# Sensors.net
KiCad netlist of a schematic drawn in Altium Designer
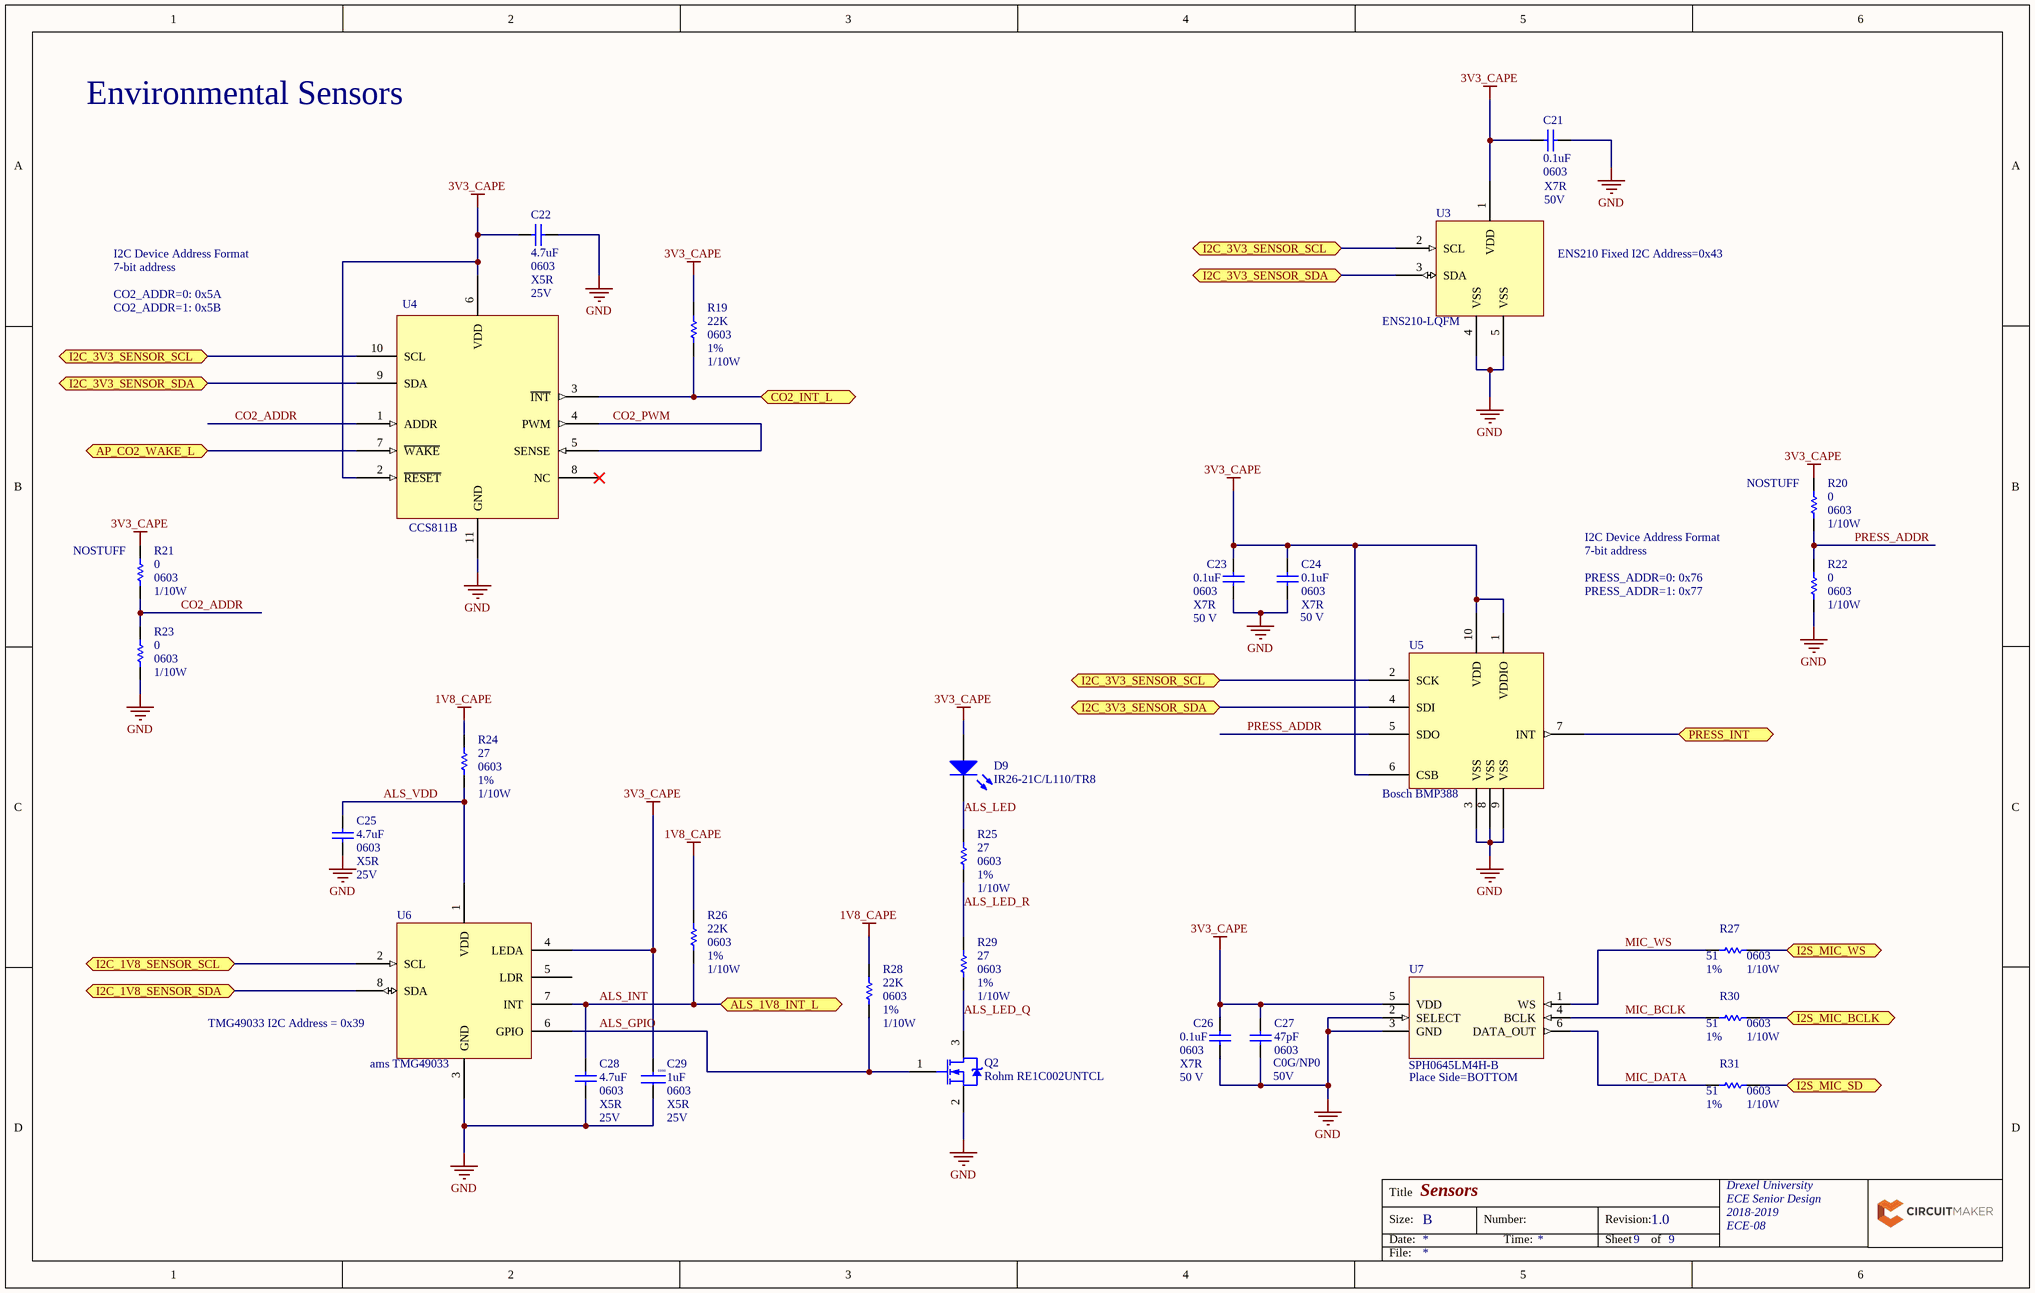
[diagram p0: Sensors.SchDoc]

(export (version "E")
  (design (tool "Eeschema 10.0.6"))
  (components
    (comp (ref "C21")
      (value "Yageo CC0603JRX7R9BB104")
      (footprint "PCB-8khfq59xjr5zuwyx680t-1")
      (description "0603 0.1 uF 50 V ±5 % Tolerance X7R SMT Multilayer Ceramic Capacitor")
      (fields
        (field (name "MANUFACTURER PART NUMBER") "CC0603JRX7R9BB104")
        (field (name "CAPACITANCE") "0.1uF")
        (field (name "CASE/PACKAGE") "0603")
        (field (name "VOLTAGE RATING (DC)") "50V")
        (field (name "DIELECTRIC CHARACTERISTIC") "X7R")
      )
      (libsource (lib "CommunityVault") (part "CMP-d32a1ae46a380ced-1"))
    )
    (comp (ref "C22")
      (value "Murata GRM188R61E475KE11D")
      (footprint "CAPC1608X90X35ML10T15")
      (description "CAP CER 4.7UF 25V 10% X5R 0603")
      (fields
        (field (name "CAPACITANCE") "4.7uF")
        (field (name "CASE/PACKAGE") "0603")
        (field (name "DIELECTRIC CHARACTERISTIC") "X5R")
        (field (name "VOLTAGE RATING (DC)") "25V")
        (field (name "MANUFACTURER PART NUMBER") "GRM188R61E475KE11D")
      )
      (libsource (lib "CommunityVault") (part "CMP-8856396-4"))
    )
    (comp (ref "C23")
      (value "Yageo CC0603JRX7R9BB104")
      (footprint "PCB-8khfq59xjr5zuwyx680t-1")
      (description "0603 0.1 uF 50 V ±5 % Tolerance X7R SMT Multilayer Ceramic Capacitor")
      (fields
        (field (name "MANUFACTURER PART NUMBER") "CC0603JRX7R9BB104")
        (field (name "CAPACITANCE") "0.1uF")
        (field (name "CASE/PACKAGE") "0603")
        (field (name "VOLTAGE RATING (DC)") "50 V")
        (field (name "DIELECTRIC CHARACTERISTIC") "X7R")
      )
      (libsource (lib "CommunityVault") (part "CMP-d32a1ae46a380ced-1"))
    )
    (comp (ref "C24")
      (value "Yageo CC0603JRX7R9BB104")
      (footprint "PCB-8khfq59xjr5zuwyx680t-1")
      (description "0603 0.1 uF 50 V ±5 % Tolerance X7R SMT Multilayer Ceramic Capacitor")
      (fields
        (field (name "MANUFACTURER PART NUMBER") "CC0603JRX7R9BB104")
        (field (name "CAPACITANCE") "0.1uF")
        (field (name "CASE/PACKAGE") "0603")
        (field (name "VOLTAGE RATING (DC)") "50 V")
        (field (name "DIELECTRIC CHARACTERISTIC") "X7R")
      )
      (libsource (lib "CommunityVault") (part "CMP-d32a1ae46a380ced-1"))
    )
    (comp (ref "C25")
      (value "Murata GRM188R61E475KE11D")
      (footprint "CAPC1608X90X35ML10T15")
      (description "CAP CER 4.7UF 25V 10% X5R 0603")
      (fields
        (field (name "CAPACITANCE") "4.7uF")
        (field (name "CASE/PACKAGE") "0603")
        (field (name "DIELECTRIC CHARACTERISTIC") "X5R")
        (field (name "VOLTAGE RATING (DC)") "25V")
        (field (name "MANUFACTURER PART NUMBER") "GRM188R61E475KE11D")
      )
      (libsource (lib "CommunityVault") (part "CMP-8856396-4"))
    )
    (comp (ref "C26")
      (value "Yageo CC0603JRX7R9BB104")
      (footprint "PCB-8khfq59xjr5zuwyx680t-1")
      (description "0603 0.1 uF 50 V ±5 % Tolerance X7R SMT Multilayer Ceramic Capacitor")
      (fields
        (field (name "MANUFACTURER PART NUMBER") "CC0603JRX7R9BB104")
        (field (name "CAPACITANCE") "0.1uF")
        (field (name "CASE/PACKAGE") "0603")
        (field (name "VOLTAGE RATING (DC)") "50 V")
        (field (name "DIELECTRIC CHARACTERISTIC") "X7R")
      )
      (libsource (lib "CommunityVault") (part "CMP-d32a1ae46a380ced-1"))
    )
    (comp (ref "C27")
      (value "Würth Elektronik 885012006055")
      (footprint "PCB-6hp2bdit6vqlyhs5eujf-1")
      (description "Cap, Mlcc, Np0, 47Pf, 50V, 0603")
      (fields
        (field (name "MANUFACTURER PART NUMBER") "885012006055")
        (field (name "CAPACITANCE") "47pF")
        (field (name "DIELECTRIC CHARACTERISTIC") "C0G/NP0")
        (field (name "VOLTAGE RATING (DC)") "50V")
        (field (name "PACKAGE") "0603")
      )
      (libsource (lib "CommunityVault") (part "CMP-bdcf7723a1936208-1"))
    )
    (comp (ref "C28")
      (value "Murata GRM188R61E475KE11D")
      (footprint "CAPC1608X90X35ML10T15")
      (description "CAP CER 4.7UF 25V 10% X5R 0603")
      (fields
        (field (name "CAPACITANCE") "4.7uF")
        (field (name "CASE/PACKAGE") "0603")
        (field (name "DIELECTRIC CHARACTERISTIC") "X5R")
        (field (name "VOLTAGE RATING (DC)") "25V")
        (field (name "MANUFACTURER PART NUMBER") "GRM188R61E475KE11D")
      )
      (libsource (lib "CommunityVault") (part "CMP-8856396-4"))
    )
    (comp (ref "C29")
      (value "Taiyo Yuden TMK107BJ105KA-T")
      (footprint "PCB-bncvufzharetcg4gy1u6-1")
      (description "Cap Ceramic 1uF 25V X5R 10% SMD 0603 85°C Paper T/R")
      (fields
        (field (name "CASE/PACKAGE") "0603")
        (field (name "DIELECTRIC CHARACTERISTIC") "X5R")
        (field (name "CAPACITANCE") "1uF")
        (field (name "VOLTAGE RATING (DC)") "25V")
        (field (name "MANUFACTURER PART NUMBER") "TMK107BJ105KA-T")
      )
      (libsource (lib "CommunityVault") (part "CMP-ac4e65478e587389-1"))
    )
    (comp (ref "D9")
      (value "IR26-21C/L110/TR8")
      (footprint "1206_A")
      (description "LED IR SUBMINI 1.6MM ROUND SMD")
      (libsource (lib "CommunityVault") (part "CMP-1542916-2"))
    )
    (comp (ref "Q2")
      (value "Rohm RE1C002UNTCL")
      (footprint "PCB-cy8fr5d7bejv46iuepu9-1")
      (description "MOSFET N-CH 20V 0.2A EMT3")
      (fields
        (field (name "MANUFACTURER") "Rohm Semiconductor")
        (field (name "MANUFACTURER PART NUMBER") "RE1C002UNTCL")
      )
      (libsource (lib "CommunityVault") (part "SYM-817649b5405f5eb1-1"))
    )
    (comp (ref "R19")
      (value "Yageo RC0603FR-0722KL")
      (footprint "RESC1608X55X25LL10T15")
      (description "Chip Resistor, 22 KOhm, +/- 1%, 0.1 W, -55 to 155 degC, 0603 (1608 Metric), RoHS, Tape and Reel")
      (fields
        (field (name "RESISTANCE") "22K")
        (field (name "RESISTANCE TOLERANCE") "1%")
        (field (name "CASE/PACKAGE") "0603")
        (field (name "POWER RATING") "1/10W")
        (field (name "MANUFACTURER PART NUMBER") "RC0603FR-0722KL")
      )
      (libsource (lib "CommunityVault") (part "CMP-1853446-5"))
    )
    (comp (ref "R20")
      (value "Res1")
      (footprint "PCB-vghjuybc2rzv8513tm8h-1")
      (description "RES SMD 0 OHM JUMPER 1/10W 0603")
      (fields
        (field (name "SUPPLIER DEVICE PACKAGE") "0603")
        (field (name "MANUFACTURER PART NUMBER") "RC0603JR-070RL")
        (field (name "RESISTANCE") "0")
        (field (name "POWER") "1/10W")
        (field (name "ALTIUM_UNNAMED_1") "NOSTUFF")
      )
      (libsource (lib "CommunityVault") (part "CMP-536b9a7387ce8cac-9"))
    )
    (comp (ref "R21")
      (value "Res1")
      (footprint "PCB-vghjuybc2rzv8513tm8h-1")
      (description "RES SMD 0 OHM JUMPER 1/10W 0603")
      (fields
        (field (name "SUPPLIER DEVICE PACKAGE") "0603")
        (field (name "MANUFACTURER PART NUMBER") "RC0603JR-070RL")
        (field (name "RESISTANCE") "0")
        (field (name "POWER") "1/10W")
        (field (name "ALTIUM_UNNAMED_1") "NOSTUFF")
      )
      (libsource (lib "CommunityVault") (part "CMP-536b9a7387ce8cac-9"))
    )
    (comp (ref "R22")
      (value "Res1")
      (footprint "PCB-vghjuybc2rzv8513tm8h-1")
      (description "RES SMD 0 OHM JUMPER 1/10W 0603")
      (fields
        (field (name "SUPPLIER DEVICE PACKAGE") "0603")
        (field (name "MANUFACTURER PART NUMBER") "RC0603JR-070RL")
        (field (name "RESISTANCE") "0")
        (field (name "POWER") "1/10W")
      )
      (libsource (lib "CommunityVault") (part "CMP-536b9a7387ce8cac-9"))
    )
    (comp (ref "R23")
      (value "Res1")
      (footprint "PCB-vghjuybc2rzv8513tm8h-1")
      (description "RES SMD 0 OHM JUMPER 1/10W 0603")
      (fields
        (field (name "SUPPLIER DEVICE PACKAGE") "0603")
        (field (name "MANUFACTURER PART NUMBER") "RC0603JR-070RL")
        (field (name "RESISTANCE") "0")
        (field (name "POWER") "1/10W")
      )
      (libsource (lib "CommunityVault") (part "CMP-536b9a7387ce8cac-9"))
    )
    (comp (ref "R24")
      (value "Panasonic / Panasonic ECG ERJ-3EKF27R0V")
      (footprint "0603-RES")
      (description "Res Thick Film 0603 27 Ohm 1% 0.1W(1/10W) ±100ppm/C Molded SMD Automotive Punched T/R")
      (fields
        (field (name "MANUFACTURER PART NUMBER") "ERJ-3EKF27R0V")
        (field (name "RESISTANCE") "27")
        (field (name "POWER RATING") "1/10W")
        (field (name "CASE/PACKAGE") "0603")
        (field (name "RESISTANCE TOLERANCE") "1%")
      )
      (libsource (lib "CommunityVault") (part "CMP-f61f3f990ffb29d8-2"))
    )
    (comp (ref "R25")
      (value "Panasonic / Panasonic ECG ERJ-3EKF27R0V")
      (footprint "0603-RES")
      (description "Res Thick Film 0603 27 Ohm 1% 0.1W(1/10W) ±100ppm/C Molded SMD Automotive Punched T/R")
      (fields
        (field (name "MANUFACTURER PART NUMBER") "ERJ-3EKF27R0V")
        (field (name "RESISTANCE") "27")
        (field (name "POWER RATING") "1/10W")
        (field (name "CASE/PACKAGE") "0603")
        (field (name "RESISTANCE TOLERANCE") "1%")
      )
      (libsource (lib "CommunityVault") (part "CMP-f61f3f990ffb29d8-2"))
    )
    (comp (ref "R26")
      (value "Yageo RC0603FR-0722KL")
      (footprint "RESC1608X55X25LL10T15")
      (description "Chip Resistor, 22 KOhm, +/- 1%, 0.1 W, -55 to 155 degC, 0603 (1608 Metric), RoHS, Tape and Reel")
      (fields
        (field (name "RESISTANCE") "22K")
        (field (name "RESISTANCE TOLERANCE") "1%")
        (field (name "CASE/PACKAGE") "0603")
        (field (name "POWER RATING") "1/10W")
        (field (name "MANUFACTURER PART NUMBER") "RC0603FR-0722KL")
      )
      (libsource (lib "CommunityVault") (part "CMP-1853446-5"))
    )
    (comp (ref "R27")
      (value "Stackpole Electronics RMCF0603FT51R0")
      (footprint "PCB-9ahxsq8gddjqcnfjmojj-1")
      (description "Res Thick Film 0603 51 Ohm 1% 0.1W(1/10W) ???}100ppm/??? Molded SMD Automotive Paper T/R")
      (fields
        (field (name "CASE/PACKAGE") "0603")
        (field (name "MANUFACTURER PART NUMBER") "RMCF0603FT51R0")
        (field (name "POWER RATING") "1/10W")
        (field (name "RESISTANCE") "51")
        (field (name "RESISTANCE TOLERANCE") "1%")
      )
      (libsource (lib "CommunityVault") (part "CMP-c18a09a5cf0a1e4d-2"))
    )
    (comp (ref "R28")
      (value "Yageo RC0603FR-0722KL")
      (footprint "RESC1608X55X25LL10T15")
      (description "Chip Resistor, 22 KOhm, +/- 1%, 0.1 W, -55 to 155 degC, 0603 (1608 Metric), RoHS, Tape and Reel")
      (fields
        (field (name "RESISTANCE") "22K")
        (field (name "RESISTANCE TOLERANCE") "1%")
        (field (name "CASE/PACKAGE") "0603")
        (field (name "POWER RATING") "1/10W")
        (field (name "MANUFACTURER PART NUMBER") "RC0603FR-0722KL")
      )
      (libsource (lib "CommunityVault") (part "CMP-1853446-5"))
    )
    (comp (ref "R29")
      (value "Panasonic / Panasonic ECG ERJ-3EKF27R0V")
      (footprint "0603-RES")
      (description "Res Thick Film 0603 27 Ohm 1% 0.1W(1/10W) ±100ppm/C Molded SMD Automotive Punched T/R")
      (fields
        (field (name "MANUFACTURER PART NUMBER") "ERJ-3EKF27R0V")
        (field (name "RESISTANCE") "27")
        (field (name "POWER RATING") "1/10W")
        (field (name "CASE/PACKAGE") "0603")
        (field (name "RESISTANCE TOLERANCE") "1%")
      )
      (libsource (lib "CommunityVault") (part "CMP-f61f3f990ffb29d8-2"))
    )
    (comp (ref "R30")
      (value "Stackpole Electronics RMCF0603FT51R0")
      (footprint "PCB-9ahxsq8gddjqcnfjmojj-1")
      (description "Res Thick Film 0603 51 Ohm 1% 0.1W(1/10W) ???}100ppm/??? Molded SMD Automotive Paper T/R")
      (fields
        (field (name "CASE/PACKAGE") "0603")
        (field (name "MANUFACTURER PART NUMBER") "RMCF0603FT51R0")
        (field (name "POWER RATING") "1/10W")
        (field (name "RESISTANCE") "51")
        (field (name "RESISTANCE TOLERANCE") "1%")
      )
      (libsource (lib "CommunityVault") (part "CMP-c18a09a5cf0a1e4d-2"))
    )
    (comp (ref "R31")
      (value "Stackpole Electronics RMCF0603FT51R0")
      (footprint "PCB-9ahxsq8gddjqcnfjmojj-1")
      (description "Res Thick Film 0603 51 Ohm 1% 0.1W(1/10W) ???}100ppm/??? Molded SMD Automotive Paper T/R")
      (fields
        (field (name "CASE/PACKAGE") "0603")
        (field (name "MANUFACTURER PART NUMBER") "RMCF0603FT51R0")
        (field (name "POWER RATING") "1/10W")
        (field (name "RESISTANCE") "51")
        (field (name "RESISTANCE TOLERANCE") "1%")
      )
      (libsource (lib "CommunityVault") (part "CMP-c18a09a5cf0a1e4d-2"))
    )
    (comp (ref "U3")
      (value "ENS210-LQFM")
      (footprint "DFN95P200X80-4N")
      (description "Humidity/Temperature Sensor Digital Serial (2-Wire, I2C) 4-Pin QFN EP T/R")
      (libsource (lib "CommunityVault") (part "CMP-d38f1e156f1a0c48-1"))
    )
    (comp (ref "U4")
      (value "CCS811B")
      (footprint "CCS811B")
      (description "Low Power Digital Sensor For Ind")
      (fields (field (name "MANUFACTURER PART NUMBER") "CCS811B-JOPD500"))
      (libsource (lib "CommunityVault") (part "CMP-1175dd4b038fceb2-3"))
    )
    (comp (ref "U5")
      (value "Bosch BMP388")
      (footprint "BMP388")
      (description "Pressure Sensor by Bosch Sensortec")
      (fields (field (name "MANUFACTURER PART NUMBER") "BMP388"))
      (libsource (lib "CommunityVault") (part "CMP-7accb6959f30a50b-7"))
    )
    (comp (ref "U6")
      (value "ams TMG49033")
      (footprint "LGA8C102P2X4_200X500X107")
      (description "Gesture, Color and Proximity Sensor Module Digital Output 1.8V 8-Pin T/R")
      (libsource (lib "CommunityVault") (part "CMP-5d86977545368241-2"))
    )
    (comp (ref "U7")
      (value "PH0645LM4H-B")
      (footprint "SPH-MEMS")
      (description "Mic Mems Digital I2s Omni -26db")
      (fields (field (name "MANUFACTURER PART NUMBER") "SPH0645LM4H-B"))
      (libsource (lib "CommunityVault") (part "CMP-f6813c2c61792946-5"))
    )
  )
  (nets
    (net (code "1") (name "/ALS_GPIO") (class "Default")
      (node (ref "Q2") (pin "1") (pinfunction "G_1") (pintype "passive"))
      (node (ref "R28") (pin "1") (pinfunction "1_1") (pintype "passive"))
      (node (ref "U6") (pin "6") (pinfunction "GPIO_6") (pintype "open_collector"))
    )
    (net (code "2") (name "/ALS_INT") (class "Default")
      (node (ref "C28") (pin "1") (pinfunction "1_1") (pintype "passive"))
      (node (ref "R26") (pin "1") (pinfunction "1_1") (pintype "passive"))
      (node (ref "U6") (pin "7") (pinfunction "INT_7") (pintype "open_collector"))
    )
    (net (code "3") (name "/ALS_LED") (class "Default")
      (node (ref "D9") (pin "2") (pinfunction "2_2") (pintype "passive"))
      (node (ref "R25") (pin "2") (pinfunction "2_2") (pintype "passive"))
    )
    (net (code "4") (name "/ALS_LED_Q") (class "Default")
      (node (ref "Q2") (pin "3") (pinfunction "D_3") (pintype "passive"))
      (node (ref "R29") (pin "1") (pinfunction "1_1") (pintype "passive"))
    )
    (net (code "5") (name "/ALS_LED_R") (class "Default")
      (node (ref "R25") (pin "1") (pinfunction "1_1") (pintype "passive"))
      (node (ref "R29") (pin "2") (pinfunction "2_2") (pintype "passive"))
    )
    (net (code "6") (name "/ALS_VDD") (class "Default")
      (node (ref "C25") (pin "1") (pinfunction "1_1") (pintype "passive"))
      (node (ref "R24") (pin "1") (pinfunction "1_1") (pintype "passive"))
      (node (ref "U6") (pin "1") (pinfunction "VDD_1") (pintype "power_in"))
    )
    (net (code "7") (name "/AP_CO2_WAKE_L") (class "Default")
      (node (ref "U4") (pin "7") (pinfunction "~{WAKE}_7") (pintype "input"))
    )
    (net (code "8") (name "/CO2_ADDR") (class "Default")
      (node (ref "R21") (pin "1") (pinfunction "1_1") (pintype "passive"))
      (node (ref "R23") (pin "2") (pinfunction "2_2") (pintype "passive"))
      (node (ref "U4") (pin "1") (pinfunction "ADDR_1") (pintype "input"))
    )
    (net (code "9") (name "/CO2_INT_L") (class "Default")
      (node (ref "R19") (pin "1") (pinfunction "1_1") (pintype "passive"))
      (node (ref "U4") (pin "3") (pinfunction "~{INT}_3") (pintype "output"))
    )
    (net (code "10") (name "/CO2_PWM") (class "Default")
      (node (ref "U4") (pin "4") (pinfunction "PWM_4") (pintype "output"))
      (node (ref "U4") (pin "5") (pinfunction "SENSE_5") (pintype "input"))
    )
    (net (code "11") (name "/I2C_1V8_SENSOR_SCL") (class "Default")
      (node (ref "U6") (pin "2") (pinfunction "SCL_2") (pintype "input"))
    )
    (net (code "12") (name "/I2C_1V8_SENSOR_SDA") (class "Default")
      (node (ref "U6") (pin "8") (pinfunction "SDA_8") (pintype "bidirectional"))
    )
    (net (code "13") (name "/I2C_3V3_SENSOR_SCL") (class "Default")
      (node (ref "U3") (pin "2") (pinfunction "SCL_2") (pintype "input"))
      (node (ref "U4") (pin "10") (pinfunction "SCL_10") (pintype "open_collector"))
      (node (ref "U5") (pin "2") (pinfunction "SCK_2") (pintype "passive"))
    )
    (net (code "14") (name "/I2C_3V3_SENSOR_SDA") (class "Default")
      (node (ref "U3") (pin "3") (pinfunction "SDA_3") (pintype "bidirectional"))
      (node (ref "U4") (pin "9") (pinfunction "SDA_9") (pintype "open_collector"))
      (node (ref "U5") (pin "4") (pinfunction "SDI_4") (pintype "passive"))
    )
    (net (code "15") (name "/I2S_MIC_BCLK") (class "Default")
      (node (ref "R30") (pin "2") (pinfunction "2_2") (pintype "passive"))
    )
    (net (code "16") (name "/I2S_MIC_SD") (class "Default")
      (node (ref "R31") (pin "2") (pinfunction "2_2") (pintype "passive"))
    )
    (net (code "17") (name "/I2S_MIC_WS") (class "Default")
      (node (ref "R27") (pin "2") (pinfunction "2_2") (pintype "passive"))
    )
    (net (code "18") (name "/MIC_BCLK") (class "Default")
      (node (ref "R30") (pin "1") (pinfunction "1_1") (pintype "passive"))
      (node (ref "U7") (pin "4") (pinfunction "BCLK_4") (pintype "input"))
    )
    (net (code "19") (name "/MIC_DATA") (class "Default")
      (node (ref "R31") (pin "1") (pinfunction "1_1") (pintype "passive"))
      (node (ref "U7") (pin "6") (pinfunction "DATA_OUT_6") (pintype "output"))
    )
    (net (code "20") (name "/MIC_WS") (class "Default")
      (node (ref "R27") (pin "1") (pinfunction "1_1") (pintype "passive"))
      (node (ref "U7") (pin "1") (pinfunction "WS_1") (pintype "input"))
    )
    (net (code "21") (name "/PRESS_ADDR") (class "Default")
      (node (ref "R20") (pin "1") (pinfunction "1_1") (pintype "passive"))
      (node (ref "R22") (pin "2") (pinfunction "2_2") (pintype "passive"))
      (node (ref "U5") (pin "5") (pinfunction "SDO_5") (pintype "passive"))
    )
    (net (code "22") (name "/PRESS_INT") (class "Default")
      (node (ref "U5") (pin "7") (pinfunction "INT_7") (pintype "output"))
    )
    (net (code "23") (name "1V8_CAPE") (class "Default")
      (node (ref "R24") (pin "2") (pinfunction "2_2") (pintype "passive"))
      (node (ref "R26") (pin "2") (pinfunction "2_2") (pintype "passive"))
      (node (ref "R28") (pin "2") (pinfunction "2_2") (pintype "passive"))
    )
    (net (code "24") (name "3V3_CAPE") (class "Default")
      (node (ref "C21") (pin "2") (pinfunction "2_2") (pintype "passive"))
      (node (ref "C22") (pin "2") (pinfunction "2_2") (pintype "passive"))
      (node (ref "C23") (pin "2") (pinfunction "2_2") (pintype "passive"))
      (node (ref "C24") (pin "2") (pinfunction "2_2") (pintype "passive"))
      (node (ref "C26") (pin "2") (pinfunction "2_2") (pintype "passive"))
      (node (ref "C27") (pin "2") (pinfunction "2_2") (pintype "passive"))
      (node (ref "C29") (pin "2") (pinfunction "2_2") (pintype "passive"))
      (node (ref "D9") (pin "1") (pinfunction "1_1") (pintype "passive"))
      (node (ref "R19") (pin "2") (pinfunction "2_2") (pintype "passive"))
      (node (ref "R20") (pin "2") (pinfunction "2_2") (pintype "passive"))
      (node (ref "R21") (pin "2") (pinfunction "2_2") (pintype "passive"))
      (node (ref "U3") (pin "1") (pinfunction "VDD_1") (pintype "power_in"))
      (node (ref "U4") (pin "2") (pinfunction "~{RESET}_2") (pintype "input"))
      (node (ref "U4") (pin "6") (pinfunction "VDD_6") (pintype "power_in"))
      (node (ref "U5") (pin "1") (pinfunction "VDDIO_1") (pintype "power_in"))
      (node (ref "U5") (pin "10") (pinfunction "VDD_10") (pintype "power_in"))
      (node (ref "U5") (pin "6") (pinfunction "CSB_6") (pintype "passive"))
      (node (ref "U6") (pin "4") (pinfunction "LEDA_4") (pintype "passive"))
      (node (ref "U7") (pin "5") (pinfunction "VDD_5") (pintype "power_in"))
    )
    (net (code "25") (name "GND") (class "Default")
      (node (ref "C21") (pin "1") (pinfunction "1_1") (pintype "passive"))
      (node (ref "C22") (pin "1") (pinfunction "1_1") (pintype "passive"))
      (node (ref "C23") (pin "1") (pinfunction "1_1") (pintype "passive"))
      (node (ref "C24") (pin "1") (pinfunction "1_1") (pintype "passive"))
      (node (ref "C25") (pin "2") (pinfunction "2_2") (pintype "passive"))
      (node (ref "C26") (pin "1") (pinfunction "1_1") (pintype "passive"))
      (node (ref "C27") (pin "1") (pinfunction "1_1") (pintype "passive"))
      (node (ref "C28") (pin "2") (pinfunction "2_2") (pintype "passive"))
      (node (ref "C29") (pin "1") (pinfunction "1_1") (pintype "passive"))
      (node (ref "Q2") (pin "2") (pinfunction "S_2") (pintype "passive"))
      (node (ref "R22") (pin "1") (pinfunction "1_1") (pintype "passive"))
      (node (ref "R23") (pin "1") (pinfunction "1_1") (pintype "passive"))
      (node (ref "U3") (pin "4") (pinfunction "VSS_4") (pintype "power_in"))
      (node (ref "U3") (pin "5") (pinfunction "VSS_5") (pintype "power_in"))
      (node (ref "U4") (pin "11") (pinfunction "GND_11") (pintype "power_in"))
      (node (ref "U5") (pin "3") (pinfunction "VSS_3") (pintype "power_in"))
      (node (ref "U5") (pin "8") (pinfunction "VSS_8") (pintype "power_in"))
      (node (ref "U5") (pin "9") (pinfunction "VSS_9") (pintype "power_in"))
      (node (ref "U6") (pin "3") (pinfunction "GND_3") (pintype "power_in"))
      (node (ref "U7") (pin "2") (pinfunction "SELECT_2") (pintype "input"))
      (node (ref "U7") (pin "3") (pinfunction "GND_3") (pintype "power_in"))
    )
    (net (code "26") (name "unconnected-(U4-NC-Pad8)") (class "Default")
      (node (ref "U4") (pin "8") (pinfunction "NC_8") (pintype "passive+no_connect"))
    )
    (net (code "27") (name "unconnected-(U6-LDR-Pad5)") (class "Default")
      (node (ref "U6") (pin "5") (pinfunction "LDR_5") (pintype "passive"))
    )
  )
)
